# UC3842.net
KiCad netlist of a schematic drawn in Altium Designer
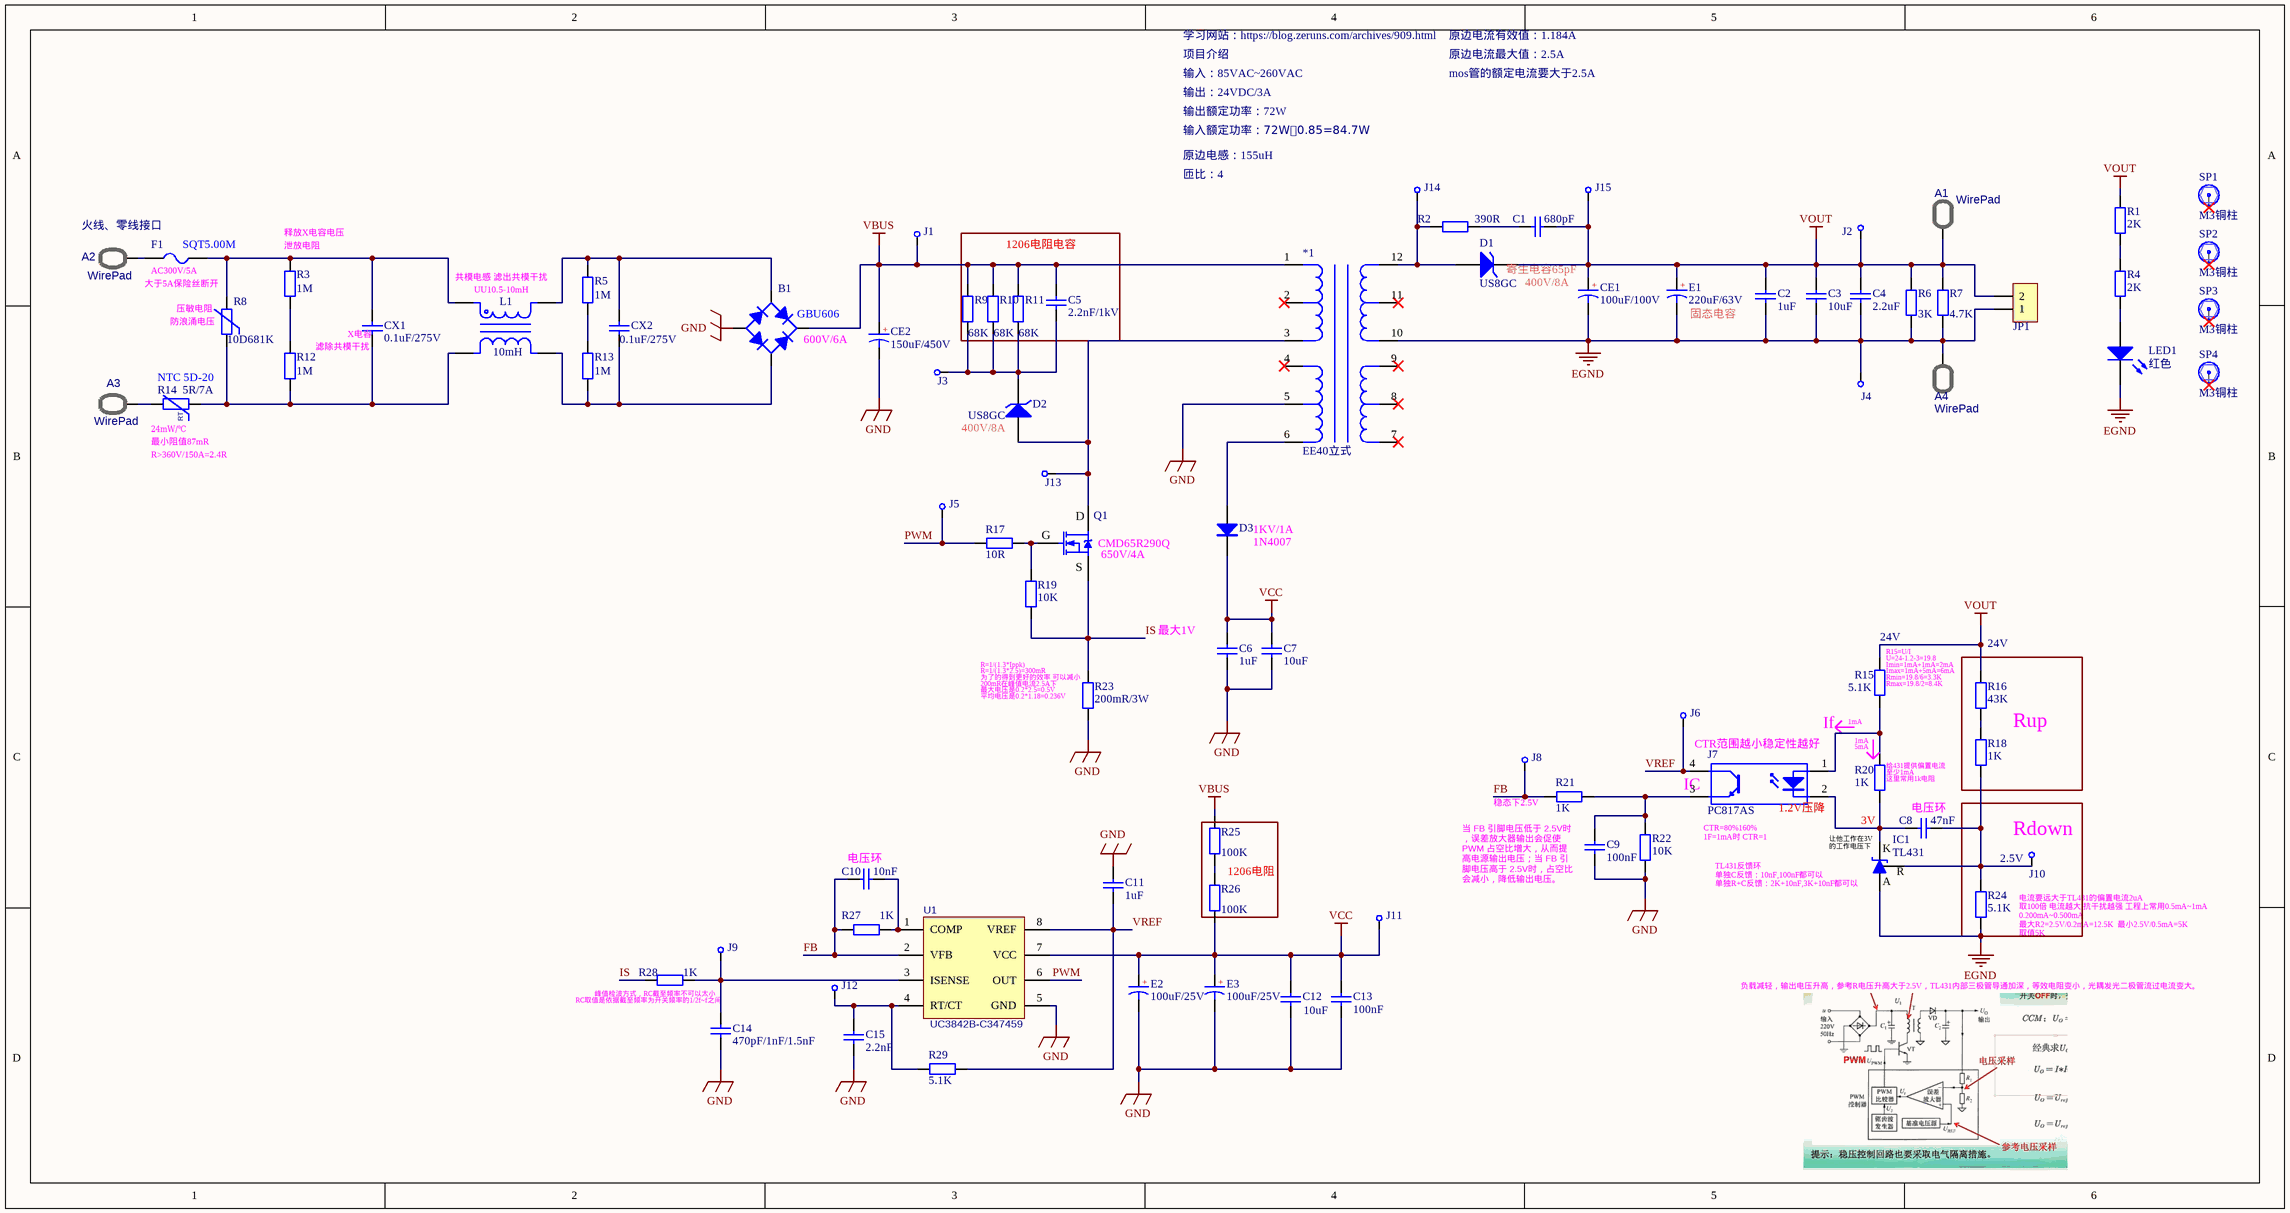
[diagram p0: UC3842第三版.SchDoc]

(export (version "E")
  (design (tool "Eeschema 10.0.6"))
  (components
    (comp (ref "*1") (value "EE40立式") (footprint "EE40立式") (libsource (lib "1.4 - 继电器-变压器") (part "EE40立式")))
    (comp (ref "A1")
      (value "WirePad")
      (footprint "WirePad-4.5x7")
      (description "线缆焊盘")
      (libsource (lib "无刷驱动-STC-无感-Lite3S") (part "WirePad"))
    )
    (comp (ref "A2")
      (value "WirePad")
      (footprint "WirePad-4.5x7")
      (description "线缆焊盘")
      (libsource (lib "无刷驱动-STC-无感-Lite3S") (part "WirePad"))
    )
    (comp (ref "A3")
      (value "WirePad")
      (footprint "WirePad-4.5x7")
      (description "线缆焊盘")
      (libsource (lib "无刷驱动-STC-无感-Lite3S") (part "WirePad"))
    )
    (comp (ref "A4")
      (value "WirePad")
      (footprint "WirePad-4.5x7")
      (description "线缆焊盘")
      (libsource (lib "无刷驱动-STC-无感-Lite3S") (part "WirePad"))
    )
    (comp (ref "B1")
      (value "GBU606")
      (footprint "GBU")
      (description "1KV/10A整流桥")
      (libsource (lib "0.2 - 二极管-TVS-ESD-整流桥-放电管") (part "GBU"))
    )
    (comp (ref "C1")
      (value "680pF")
      (footprint "C0805_L")
      (description "贴片电容/MLCC电容")
      (libsource (lib "0.1 - 电阻-电容-电感-保险丝-晶振-晶体-磁珠-电位器-法拉电容-馈通电容") (part "C"))
    )
    (comp (ref "C2")
      (value "1uF")
      (footprint "C0805_L")
      (description "贴片电容/MLCC电容")
      (libsource (lib "0.1 - 电阻-电容-电感-保险丝-晶振-晶体-磁珠-电位器-法拉电容-馈通电容") (part "C"))
    )
    (comp (ref "C3")
      (value "10uF")
      (footprint "C0805_L")
      (description "贴片电容/MLCC电容")
      (libsource (lib "0.1 - 电阻-电容-电感-保险丝-晶振-晶体-磁珠-电位器-法拉电容-馈通电容") (part "C"))
    )
    (comp (ref "C4")
      (value "2.2uF")
      (footprint "C0805_L")
      (description "贴片电容/MLCC电容")
      (libsource (lib "0.1 - 电阻-电容-电感-保险丝-晶振-晶体-磁珠-电位器-法拉电容-馈通电容") (part "C"))
    )
    (comp (ref "C5")
      (value "2.2nF/1kV")
      (footprint "C0805_L")
      (description "贴片电容/MLCC电容")
      (libsource (lib "0.1 - 电阻-电容-电感-保险丝-晶振-晶体-磁珠-电位器-法拉电容-馈通电容") (part "C"))
    )
    (comp (ref "C6")
      (value "1uF")
      (footprint "C0805_L")
      (description "贴片电容/MLCC电容")
      (libsource (lib "0.1 - 电阻-电容-电感-保险丝-晶振-晶体-磁珠-电位器-法拉电容-馈通电容") (part "C"))
    )
    (comp (ref "C7")
      (value "10uF")
      (footprint "C0805_L")
      (description "贴片电容/MLCC电容")
      (libsource (lib "0.1 - 电阻-电容-电感-保险丝-晶振-晶体-磁珠-电位器-法拉电容-馈通电容") (part "C"))
    )
    (comp (ref "C8")
      (value "47nF")
      (footprint "C0805_L")
      (description "贴片电容/MLCC电容")
      (libsource (lib "0.1 - 电阻-电容-电感-保险丝-晶振-晶体-磁珠-电位器-法拉电容-馈通电容") (part "C"))
    )
    (comp (ref "C9")
      (value "100nF")
      (footprint "C0805_L")
      (description "贴片电容/MLCC电容")
      (libsource (lib "0.1 - 电阻-电容-电感-保险丝-晶振-晶体-磁珠-电位器-法拉电容-馈通电容") (part "C"))
    )
    (comp (ref "C10")
      (value "10nF")
      (footprint "C0805_L")
      (description "贴片电容/MLCC电容")
      (libsource (lib "0.1 - 电阻-电容-电感-保险丝-晶振-晶体-磁珠-电位器-法拉电容-馈通电容") (part "C"))
    )
    (comp (ref "C11")
      (value "1uF")
      (footprint "C0805_L")
      (description "贴片电容/MLCC电容")
      (libsource (lib "0.1 - 电阻-电容-电感-保险丝-晶振-晶体-磁珠-电位器-法拉电容-馈通电容") (part "C"))
    )
    (comp (ref "C12")
      (value "10uF")
      (footprint "C0805_L")
      (description "贴片电容/MLCC电容")
      (libsource (lib "0.1 - 电阻-电容-电感-保险丝-晶振-晶体-磁珠-电位器-法拉电容-馈通电容") (part "C"))
    )
    (comp (ref "C13")
      (value "100nF")
      (footprint "C0805_L")
      (description "贴片电容/MLCC电容")
      (libsource (lib "0.1 - 电阻-电容-电感-保险丝-晶振-晶体-磁珠-电位器-法拉电容-馈通电容") (part "C"))
    )
    (comp (ref "C14")
      (value "470pF/1nF/1.5nF")
      (footprint "C0805_L")
      (description "贴片电容/MLCC电容")
      (libsource (lib "0.1 - 电阻-电容-电感-保险丝-晶振-晶体-磁珠-电位器-法拉电容-馈通电容") (part "C"))
    )
    (comp (ref "C15")
      (value "2.2nF")
      (footprint "C0805_L")
      (description "贴片电容/MLCC电容")
      (libsource (lib "0.1 - 电阻-电容-电感-保险丝-晶振-晶体-磁珠-电位器-法拉电容-馈通电容") (part "C"))
    )
    (comp (ref "CE1")
      (value "100uF/100V")
      (footprint "CE-5.0*10*16")
      (description "直插电解电容")
      (libsource (lib "0.1 - 电阻-电容-电感-保险丝-晶振-晶体-磁珠-电位器-法拉电容-馈通电容") (part "CE"))
    )
    (comp (ref "CE2")
      (value "150uF/450V")
      (footprint "CE-7.5*18*35.5-H - BK")
      (description "直插电解电容")
      (libsource (lib "0.1 - 电阻-电容-电感-保险丝-晶振-晶体-磁珠-电位器-法拉电容-馈通电容") (part "CE"))
    )
    (comp (ref "CX1")
      (value "0.1uF/275V")
      (footprint "CX 10*13*11")
      (description "安规X电容")
      (libsource (lib "0.1 - 电阻-电容-电感-保险丝-晶振-晶体-磁珠-电位器-法拉电容-馈通电容") (part "CX"))
    )
    (comp (ref "CX2")
      (value "0.1uF/275V")
      (footprint "CX 10*13*11")
      (description "安规X电容")
      (libsource (lib "0.1 - 电阻-电容-电感-保险丝-晶振-晶体-磁珠-电位器-法拉电容-馈通电容") (part "CX"))
    )
    (comp (ref "D1")
      (value "US8GC")
      (footprint "SMC")
      (description "5000W 24V TVS二极管")
      (libsource (lib "0.2 - 二极管-TVS-ESD-整流桥-放电管") (part "5.0SMDJ24A"))
    )
    (comp (ref "D2")
      (value "US8GC")
      (footprint "SMC")
      (description "5000W 24V TVS二极管")
      (libsource (lib "0.2 - 二极管-TVS-ESD-整流桥-放电管") (part "5.0SMDJ24A"))
    )
    (comp (ref "D3")
      (value "1N4007")
      (footprint "SMA")
      (description "整流二极管")
      (libsource (lib "0.2 - 二极管-TVS-ESD-整流桥-放电管") (part "1N4007"))
    )
    (comp (ref "E1")
      (value "220uF/63V")
      (footprint "CT 5.0*10*13 - R")
      (description "直插固态电容")
      (libsource (lib "0.1 - 电阻-电容-电感-保险丝-晶振-晶体-磁珠-电位器-法拉电容-馈通电容") (part "CS"))
    )
    (comp (ref "E2")
      (value "100uF/25V")
      (footprint "CE D(6.3*5.4)")
      (description "贴片电解电容")
      (libsource (lib "0.1 - 电阻-电容-电感-保险丝-晶振-晶体-磁珠-电位器-法拉电容-馈通电容") (part "CE_SMD"))
    )
    (comp (ref "E3")
      (value "100uF/25V")
      (footprint "CE D(6.3*5.4)")
      (description "贴片电解电容")
      (libsource (lib "0.1 - 电阻-电容-电感-保险丝-晶振-晶体-磁珠-电位器-法拉电容-馈通电容") (part "CE_SMD"))
    )
    (comp (ref "F1")
      (value "SQT5.00M")
      (footprint "FUSE-8.5x4.0-392Series")
      (description "方形保险丝")
      (libsource (lib "0.1 - 电阻-电容-电感-保险丝-晶振-晶体-磁珠-电位器-法拉电容-馈通电容") (part "FUSE-8.5*4.0*8.0"))
    )
    (comp (ref "IC1")
      (value "TL431")
      (footprint "SOT23-3N")
      (description "贴片可调基准稳压芯片")
      (libsource (lib "0.7 - 电源类芯片") (part "TL431_SMD"))
    )
    (comp (ref "J1")
      (value "CHECK")
      (footprint "CHECK-A")
      (description "测试点")
      (libsource (lib "课程库") (part "CHECK"))
    )
    (comp (ref "J2")
      (value "CHECK")
      (footprint "CHECK-A")
      (description "测试点")
      (libsource (lib "课程库") (part "CHECK"))
    )
    (comp (ref "J3")
      (value "CHECK")
      (footprint "CHECK-A")
      (description "测试点")
      (libsource (lib "课程库") (part "CHECK"))
    )
    (comp (ref "J4")
      (value "CHECK")
      (footprint "CHECK-A")
      (description "测试点")
      (libsource (lib "课程库") (part "CHECK"))
    )
    (comp (ref "J5")
      (value "CHECK")
      (footprint "CHECK-A")
      (description "测试点")
      (libsource (lib "课程库") (part "CHECK"))
    )
    (comp (ref "J6")
      (value "CHECK")
      (footprint "CHECK-A")
      (description "测试点")
      (libsource (lib "课程库") (part "CHECK"))
    )
    (comp (ref "J7")
      (value "PC817AS")
      (footprint "SOP4-W2.54_M")
      (description "1路开关光耦")
      (libsource (lib "0.3 - LED发光二极管-IR二极管_接收管-光耦") (part "TLP521-1"))
    )
    (comp (ref "J8")
      (value "CHECK")
      (footprint "CHECK-A")
      (description "测试点")
      (libsource (lib "课程库") (part "CHECK"))
    )
    (comp (ref "J9")
      (value "CHECK")
      (footprint "CHECK-A")
      (description "测试点")
      (libsource (lib "课程库") (part "CHECK"))
    )
    (comp (ref "J10")
      (value "CHECK")
      (footprint "CHECK-A")
      (description "测试点")
      (libsource (lib "课程库") (part "CHECK"))
    )
    (comp (ref "J11")
      (value "CHECK")
      (footprint "CHECK-A")
      (description "测试点")
      (libsource (lib "课程库") (part "CHECK"))
    )
    (comp (ref "J12")
      (value "CHECK")
      (footprint "CHECK-A")
      (description "测试点")
      (libsource (lib "课程库") (part "CHECK"))
    )
    (comp (ref "J13")
      (value "CHECK")
      (footprint "CHECK-A")
      (description "测试点")
      (libsource (lib "课程库") (part "CHECK"))
    )
    (comp (ref "J14")
      (value "CHECK")
      (footprint "CHECK-A")
      (description "测试点")
      (libsource (lib "课程库") (part "CHECK"))
    )
    (comp (ref "J15")
      (value "CHECK")
      (footprint "CHECK-A")
      (description "测试点")
      (libsource (lib "课程库") (part "CHECK"))
    )
    (comp (ref "JP1")
      (value "HDR-1X2")
      (footprint "KF301-5.0-2P")
      (description "2P接插件")
      (libsource (lib "6.0 - 5.0mm连接器(KF301-KF2EDGVHM)") (part "Header 2"))
    )
    (comp (ref "L1")
      (value "10mH")
      (footprint "UU9.8")
      (description "UU型共模电感")
      (libsource (lib "0.1 - 电阻-电容-电感-保险丝-晶振-晶体-磁珠-电位器-法拉电容-馈通电容") (part "L-UU"))
    )
    (comp (ref "LED1")
      (value "红色")
      (footprint "LED0805_G")
      (description "贴片LED")
      (libsource (lib "0.3 - LED发光二极管-IR二极管_接收管-光耦") (part "LED"))
    )
    (comp (ref "Q1")
      (value "CMD65R290Q")
      (footprint "TO252")
      (description "N沟道 100V/40A")
      (libsource (lib "0.4 - 三极管-场效应管-可控硅") (part "P40NF10L"))
    )
    (comp (ref "R1")
      (value "2K")
      (footprint "R0805_L")
      (description "贴片电阻")
      (libsource (lib "0.1 - 电阻-电容-电感-保险丝-晶振-晶体-磁珠-电位器-法拉电容-馈通电容") (part "R"))
    )
    (comp (ref "R2")
      (value "390R")
      (footprint "R0805_L")
      (description "贴片电阻")
      (libsource (lib "0.1 - 电阻-电容-电感-保险丝-晶振-晶体-磁珠-电位器-法拉电容-馈通电容") (part "R"))
    )
    (comp (ref "R3")
      (value "1M")
      (footprint "R1206_L")
      (description "贴片电阻")
      (libsource (lib "0.1 - 电阻-电容-电感-保险丝-晶振-晶体-磁珠-电位器-法拉电容-馈通电容") (part "R"))
    )
    (comp (ref "R4")
      (value "2K")
      (footprint "R0805_L")
      (description "贴片电阻")
      (libsource (lib "0.1 - 电阻-电容-电感-保险丝-晶振-晶体-磁珠-电位器-法拉电容-馈通电容") (part "R"))
    )
    (comp (ref "R5")
      (value "1M")
      (footprint "R1206_L")
      (description "贴片电阻")
      (libsource (lib "0.1 - 电阻-电容-电感-保险丝-晶振-晶体-磁珠-电位器-法拉电容-馈通电容") (part "R"))
    )
    (comp (ref "R6")
      (value "3K")
      (footprint "R1206_L")
      (description "贴片电阻")
      (libsource (lib "0.1 - 电阻-电容-电感-保险丝-晶振-晶体-磁珠-电位器-法拉电容-馈通电容") (part "R"))
    )
    (comp (ref "R7")
      (value "4.7K")
      (footprint "R1206_L")
      (description "贴片电阻")
      (libsource (lib "0.1 - 电阻-电容-电感-保险丝-晶振-晶体-磁珠-电位器-法拉电容-馈通电容") (part "R"))
    )
    (comp (ref "R8")
      (value "10D681K")
      (footprint "VDR 9D-4.5")
      (description "压敏电阻")
      (libsource (lib "0.1 - 电阻-电容-电感-保险丝-晶振-晶体-磁珠-电位器-法拉电容-馈通电容") (part "R_VSR"))
    )
    (comp (ref "R9")
      (value "68K")
      (footprint "R1206_L")
      (description "贴片电阻")
      (libsource (lib "0.1 - 电阻-电容-电感-保险丝-晶振-晶体-磁珠-电位器-法拉电容-馈通电容") (part "R"))
    )
    (comp (ref "R10")
      (value "68K")
      (footprint "R1206_L")
      (description "贴片电阻")
      (libsource (lib "0.1 - 电阻-电容-电感-保险丝-晶振-晶体-磁珠-电位器-法拉电容-馈通电容") (part "R"))
    )
    (comp (ref "R11")
      (value "68K")
      (footprint "R1206_L")
      (description "贴片电阻")
      (libsource (lib "0.1 - 电阻-电容-电感-保险丝-晶振-晶体-磁珠-电位器-法拉电容-馈通电容") (part "R"))
    )
    (comp (ref "R12")
      (value "1M")
      (footprint "R1206_L")
      (description "贴片电阻")
      (libsource (lib "0.1 - 电阻-电容-电感-保险丝-晶振-晶体-磁珠-电位器-法拉电容-馈通电容") (part "R"))
    )
    (comp (ref "R13")
      (value "1M")
      (footprint "R1206_L")
      (description "贴片电阻")
      (libsource (lib "0.1 - 电阻-电容-电感-保险丝-晶振-晶体-磁珠-电位器-法拉电容-馈通电容") (part "R"))
    )
    (comp (ref "R14")
      (value "5R/7A")
      (footprint "NTC-5D-20")
      (description "热敏电阻")
      (libsource (lib "0.1 - 电阻-电容-电感-保险丝-晶振-晶体-磁珠-电位器-法拉电容-馈通电容") (part "RT"))
    )
    (comp (ref "R15")
      (value "5.1K")
      (footprint "R0805_L")
      (description "贴片电阻")
      (libsource (lib "0.1 - 电阻-电容-电感-保险丝-晶振-晶体-磁珠-电位器-法拉电容-馈通电容") (part "R"))
    )
    (comp (ref "R16")
      (value "43K")
      (footprint "R0805_L")
      (description "贴片电阻")
      (libsource (lib "0.1 - 电阻-电容-电感-保险丝-晶振-晶体-磁珠-电位器-法拉电容-馈通电容") (part "R"))
    )
    (comp (ref "R17")
      (value "10R")
      (footprint "R0805_L")
      (description "贴片电阻")
      (libsource (lib "0.1 - 电阻-电容-电感-保险丝-晶振-晶体-磁珠-电位器-法拉电容-馈通电容") (part "R"))
    )
    (comp (ref "R18")
      (value "1K")
      (footprint "R0805_L")
      (description "贴片电阻")
      (libsource (lib "0.1 - 电阻-电容-电感-保险丝-晶振-晶体-磁珠-电位器-法拉电容-馈通电容") (part "R"))
    )
    (comp (ref "R19")
      (value "10K")
      (footprint "R0805_L")
      (description "贴片电阻")
      (libsource (lib "0.1 - 电阻-电容-电感-保险丝-晶振-晶体-磁珠-电位器-法拉电容-馈通电容") (part "R"))
    )
    (comp (ref "R20")
      (value "1K")
      (footprint "R0805_L")
      (description "贴片电阻")
      (libsource (lib "0.1 - 电阻-电容-电感-保险丝-晶振-晶体-磁珠-电位器-法拉电容-馈通电容") (part "R"))
    )
    (comp (ref "R21")
      (value "1K")
      (footprint "R0805_L")
      (description "贴片电阻")
      (libsource (lib "0.1 - 电阻-电容-电感-保险丝-晶振-晶体-磁珠-电位器-法拉电容-馈通电容") (part "R"))
    )
    (comp (ref "R22")
      (value "10K")
      (footprint "R0805_L")
      (description "贴片电阻")
      (libsource (lib "0.1 - 电阻-电容-电感-保险丝-晶振-晶体-磁珠-电位器-法拉电容-馈通电容") (part "R"))
    )
    (comp (ref "R23")
      (value "200mR/3W")
      (footprint "R2512_M")
      (description "贴片电阻")
      (libsource (lib "0.1 - 电阻-电容-电感-保险丝-晶振-晶体-磁珠-电位器-法拉电容-馈通电容") (part "R"))
    )
    (comp (ref "R24")
      (value "5.1K")
      (footprint "R0805_L")
      (description "贴片电阻")
      (libsource (lib "0.1 - 电阻-电容-电感-保险丝-晶振-晶体-磁珠-电位器-法拉电容-馈通电容") (part "R"))
    )
    (comp (ref "R25")
      (value "100K")
      (footprint "R1206_L")
      (description "贴片电阻")
      (libsource (lib "0.1 - 电阻-电容-电感-保险丝-晶振-晶体-磁珠-电位器-法拉电容-馈通电容") (part "R"))
    )
    (comp (ref "R26")
      (value "100K")
      (footprint "R1206_L")
      (description "贴片电阻")
      (libsource (lib "0.1 - 电阻-电容-电感-保险丝-晶振-晶体-磁珠-电位器-法拉电容-馈通电容") (part "R"))
    )
    (comp (ref "R27")
      (value "1K")
      (footprint "R0805_L")
      (description "贴片电阻")
      (libsource (lib "0.1 - 电阻-电容-电感-保险丝-晶振-晶体-磁珠-电位器-法拉电容-馈通电容") (part "R"))
    )
    (comp (ref "R28")
      (value "1K")
      (footprint "R0805_L")
      (description "贴片电阻")
      (libsource (lib "0.1 - 电阻-电容-电感-保险丝-晶振-晶体-磁珠-电位器-法拉电容-馈通电容") (part "R"))
    )
    (comp (ref "R29")
      (value "5.1K")
      (footprint "R0805_L")
      (description "贴片电阻")
      (libsource (lib "0.1 - 电阻-电容-电感-保险丝-晶振-晶体-磁珠-电位器-法拉电容-馈通电容") (part "R"))
    )
    (comp (ref "SP1")
      (value "M3铜柱")
      (footprint "M3x9_L")
      (description "铜柱")
      (libsource (lib "0.5 - 按键_开关_蜂鸣器_电池_测试点_Mark点_铜柱") (part "铜柱小焊盘"))
    )
    (comp (ref "SP2")
      (value "M3铜柱")
      (footprint "M3x9_L")
      (description "铜柱")
      (libsource (lib "0.5 - 按键_开关_蜂鸣器_电池_测试点_Mark点_铜柱") (part "铜柱小焊盘"))
    )
    (comp (ref "SP3")
      (value "M3铜柱")
      (footprint "M3x9_L")
      (description "铜柱")
      (libsource (lib "0.5 - 按键_开关_蜂鸣器_电池_测试点_Mark点_铜柱") (part "铜柱小焊盘"))
    )
    (comp (ref "SP4")
      (value "M3铜柱")
      (footprint "M3x9_L")
      (description "铜柱")
      (libsource (lib "0.5 - 按键_开关_蜂鸣器_电池_测试点_Mark点_铜柱") (part "铜柱小焊盘"))
    )
    (comp (ref "U1")
      (value "UC3842B-C347459")
      (footprint "SOIC-8_150mil")
      (description "开关电源芯片")
      (libsource (lib "0.7 - 电源类芯片") (part "UC3842"))
    )
  )
  (nets
    (net (code "1") (name "/FB") (class "Default")
      (node (ref "C10") (pin "2") (pinfunction "2_2") (pintype "passive"))
      (node (ref "J8") (pin "1") (pinfunction "1_1") (pintype "passive"))
      (node (ref "R21") (pin "2") (pinfunction "2_2") (pintype "passive"))
      (node (ref "R27") (pin "1") (pinfunction "1_1") (pintype "passive"))
      (node (ref "U1") (pin "2") (pinfunction "VFB_2") (pintype "passive"))
    )
    (net (code "2") (name "/IS") (class "Default")
      (node (ref "Q1") (pin "3") (pinfunction "S_3") (pintype "passive"))
      (node (ref "R19") (pin "2") (pinfunction "2_2") (pintype "passive"))
      (node (ref "R23") (pin "2") (pinfunction "2_2") (pintype "passive"))
      (node (ref "R28") (pin "1") (pinfunction "1_1") (pintype "passive"))
    )
    (net (code "3") (name "/PWM") (class "Default")
      (node (ref "J5") (pin "1") (pinfunction "1_1") (pintype "passive"))
      (node (ref "R17") (pin "2") (pinfunction "2_2") (pintype "passive"))
      (node (ref "U1") (pin "6") (pinfunction "OUT_6") (pintype "passive"))
    )
    (net (code "4") (name "/VREF") (class "Default")
      (node (ref "C11") (pin "2") (pinfunction "2_2") (pintype "passive"))
      (node (ref "J6") (pin "1") (pinfunction "1_1") (pintype "passive"))
      (node (ref "J7") (pin "4") (pinfunction "C_4") (pintype "passive"))
      (node (ref "R29") (pin "2") (pinfunction "2_2") (pintype "passive"))
      (node (ref "U1") (pin "8") (pinfunction "VREF_8") (pintype "passive"))
    )
    (net (code "5") (name "EGND") (class "Default")
      (node (ref "*1") (pin "10") (pinfunction "10_10") (pintype "passive"))
      (node (ref "A4") (pin "1") (pinfunction "1_1") (pintype "passive"))
      (node (ref "C2") (pin "1") (pinfunction "1_1") (pintype "passive"))
      (node (ref "C3") (pin "1") (pinfunction "1_1") (pintype "passive"))
      (node (ref "C4") (pin "1") (pinfunction "1_1") (pintype "passive"))
      (node (ref "CE1") (pin "2") (pinfunction "2_2") (pintype "passive"))
      (node (ref "E1") (pin "2") (pinfunction "2_2") (pintype "passive"))
      (node (ref "IC1") (pin "3") (pinfunction "A_3") (pintype "passive"))
      (node (ref "J4") (pin "1") (pinfunction "1_1") (pintype "passive"))
      (node (ref "JP1") (pin "1") (pinfunction "1_1") (pintype "passive"))
      (node (ref "LED1") (pin "2") (pinfunction "K_2") (pintype "passive"))
      (node (ref "R24") (pin "1") (pinfunction "1_1") (pintype "passive"))
      (node (ref "R6") (pin "1") (pinfunction "1_1") (pintype "passive"))
      (node (ref "R7") (pin "1") (pinfunction "1_1") (pintype "passive"))
    )
    (net (code "6") (name "GND") (class "Default")
      (node (ref "*1") (pin "5") (pinfunction "5_5") (pintype "passive"))
      (node (ref "B1") (pin "DC-") (pinfunction "DC-_DC-") (pintype "passive"))
      (node (ref "C11") (pin "1") (pinfunction "1_1") (pintype "passive"))
      (node (ref "C12") (pin "2") (pinfunction "2_2") (pintype "passive"))
      (node (ref "C13") (pin "2") (pinfunction "2_2") (pintype "passive"))
      (node (ref "C14") (pin "1") (pinfunction "1_1") (pintype "passive"))
      (node (ref "C15") (pin "1") (pinfunction "1_1") (pintype "passive"))
      (node (ref "C6") (pin "1") (pinfunction "1_1") (pintype "passive"))
      (node (ref "C7") (pin "1") (pinfunction "1_1") (pintype "passive"))
      (node (ref "C9") (pin "2") (pinfunction "2_2") (pintype "passive"))
      (node (ref "CE2") (pin "2") (pinfunction "2_2") (pintype "passive"))
      (node (ref "E2") (pin "2") (pinfunction "2_2") (pintype "passive"))
      (node (ref "E3") (pin "2") (pinfunction "2_2") (pintype "passive"))
      (node (ref "R22") (pin "2") (pinfunction "2_2") (pintype "passive"))
      (node (ref "R23") (pin "1") (pinfunction "1_1") (pintype "passive"))
      (node (ref "U1") (pin "5") (pinfunction "GND_5") (pintype "passive"))
    )
    (net (code "7") (name "Net-(A2-Pad1)") (class "Default")
      (node (ref "A2") (pin "1") (pinfunction "1_1") (pintype "passive"))
      (node (ref "F1") (pin "2") (pinfunction "2_2") (pintype "passive"))
    )
    (net (code "8") (name "Net-(A3-Pad1)") (class "Default")
      (node (ref "A3") (pin "1") (pinfunction "1_1") (pintype "passive"))
      (node (ref "R14") (pin "2") (pinfunction "2_2") (pintype "passive"))
    )
    (net (code "9") (name "Net-(B1-PadAC1)") (class "Default")
      (node (ref "B1") (pin "AC1") (pinfunction "AC1_AC1") (pintype "passive"))
      (node (ref "CX2") (pin "2") (pinfunction "2_2") (pintype "passive"))
      (node (ref "L1") (pin "2") (pinfunction "2_2") (pintype "passive"))
      (node (ref "R5") (pin "2") (pinfunction "2_2") (pintype "passive"))
    )
    (net (code "10") (name "Net-(B1-PadAC2)") (class "Default")
      (node (ref "B1") (pin "AC2") (pinfunction "AC2_AC2") (pintype "passive"))
      (node (ref "CX2") (pin "1") (pinfunction "1_1") (pintype "passive"))
      (node (ref "L1") (pin "3") (pinfunction "3_3") (pintype "passive"))
      (node (ref "R13") (pin "1") (pinfunction "1_1") (pintype "passive"))
    )
    (net (code "11") (name "Net-(C1-Pad2)") (class "Default")
      (node (ref "C1") (pin "2") (pinfunction "2_2") (pintype "passive"))
      (node (ref "R2") (pin "1") (pinfunction "1_1") (pintype "passive"))
    )
    (net (code "12") (name "Net-(CX1-Pad1)") (class "Default")
      (node (ref "CX1") (pin "1") (pinfunction "1_1") (pintype "passive"))
      (node (ref "L1") (pin "4") (pinfunction "4_4") (pintype "passive"))
      (node (ref "R12") (pin "1") (pinfunction "1_1") (pintype "passive"))
      (node (ref "R14") (pin "1") (pinfunction "1_1") (pintype "passive"))
      (node (ref "R8") (pin "1") (pinfunction "1_1") (pintype "passive"))
    )
    (net (code "13") (name "Net-(CX1-Pad2)") (class "Default")
      (node (ref "CX1") (pin "2") (pinfunction "2_2") (pintype "passive"))
      (node (ref "F1") (pin "1") (pinfunction "1_1") (pintype "passive"))
      (node (ref "L1") (pin "1") (pinfunction "1_1") (pintype "passive"))
      (node (ref "R3") (pin "2") (pinfunction "2_2") (pintype "passive"))
      (node (ref "R8") (pin "2") (pinfunction "2_2") (pintype "passive"))
    )
    (net (code "14") (name "Net-(D1-A)") (class "Default")
      (node (ref "*1") (pin "12") (pinfunction "12_12") (pintype "passive"))
      (node (ref "D1") (pin "1") (pinfunction "A_1") (pintype "passive"))
      (node (ref "J14") (pin "1") (pinfunction "1_1") (pintype "passive"))
      (node (ref "R2") (pin "2") (pinfunction "2_2") (pintype "passive"))
    )
    (net (code "15") (name "Net-(D2-A)") (class "Default")
      (node (ref "*1") (pin "3") (pinfunction "3_3") (pintype "passive"))
      (node (ref "D2") (pin "1") (pinfunction "A_1") (pintype "passive"))
      (node (ref "J13") (pin "1") (pinfunction "1_1") (pintype "passive"))
      (node (ref "Q1") (pin "2") (pintype "passive"))
    )
    (net (code "16") (name "Net-(D2-K)") (class "Default")
      (node (ref "C5") (pin "1") (pinfunction "1_1") (pintype "passive"))
      (node (ref "D2") (pin "2") (pinfunction "K_2") (pintype "passive"))
      (node (ref "J3") (pin "1") (pinfunction "1_1") (pintype "passive"))
      (node (ref "R10") (pin "1") (pinfunction "1_1") (pintype "passive"))
      (node (ref "R11") (pin "1") (pinfunction "1_1") (pintype "passive"))
      (node (ref "R9") (pin "1") (pinfunction "1_1") (pintype "passive"))
    )
    (net (code "17") (name "Net-(D3-A)") (class "Default")
      (node (ref "*1") (pin "6") (pinfunction "6_6") (pintype "passive"))
      (node (ref "D3") (pin "1") (pinfunction "A_1") (pintype "passive"))
    )
    (net (code "18") (name "Net-(IC1-K)") (class "Default")
      (node (ref "C8") (pin "2") (pinfunction "2_2") (pintype "passive"))
      (node (ref "IC1") (pin "2") (pinfunction "K_2") (pintype "passive"))
      (node (ref "J7") (pin "2") (pinfunction "K_2") (pintype "passive"))
      (node (ref "R20") (pin "1") (pinfunction "1_1") (pintype "passive"))
    )
    (net (code "19") (name "Net-(IC1-R)") (class "Default")
      (node (ref "C8") (pin "1") (pinfunction "1_1") (pintype "passive"))
      (node (ref "IC1") (pin "1") (pinfunction "R_1") (pintype "passive"))
      (node (ref "J10") (pin "1") (pinfunction "1_1") (pintype "passive"))
      (node (ref "R18") (pin "1") (pinfunction "1_1") (pintype "passive"))
      (node (ref "R24") (pin "2") (pinfunction "2_2") (pintype "passive"))
    )
    (net (code "20") (name "Net-(J7-A)") (class "Default")
      (node (ref "J7") (pin "1") (pinfunction "A_1") (pintype "passive"))
      (node (ref "R15") (pin "1") (pinfunction "1_1") (pintype "passive"))
      (node (ref "R20") (pin "2") (pinfunction "2_2") (pintype "passive"))
    )
    (net (code "21") (name "Net-(J7-E)") (class "Default")
      (node (ref "C9") (pin "1") (pinfunction "1_1") (pintype "passive"))
      (node (ref "J7") (pin "3") (pinfunction "E_3") (pintype "passive"))
      (node (ref "R21") (pin "1") (pinfunction "1_1") (pintype "passive"))
      (node (ref "R22") (pin "1") (pinfunction "1_1") (pintype "passive"))
    )
    (net (code "22") (name "Net-(LED1-A)") (class "Default")
      (node (ref "LED1") (pin "1") (pinfunction "A_1") (pintype "passive"))
      (node (ref "R4") (pin "1") (pinfunction "1_1") (pintype "passive"))
    )
    (net (code "23") (name "Net-(Q1-G)") (class "Default")
      (node (ref "Q1") (pin "1") (pinfunction "G_1") (pintype "passive"))
      (node (ref "R17") (pin "1") (pinfunction "1_1") (pintype "passive"))
      (node (ref "R19") (pin "1") (pinfunction "1_1") (pintype "passive"))
    )
    (net (code "24") (name "Net-(R1-Pad1)") (class "Default")
      (node (ref "R1") (pin "1") (pinfunction "1_1") (pintype "passive"))
      (node (ref "R4") (pin "2") (pinfunction "2_2") (pintype "passive"))
    )
    (net (code "25") (name "Net-(R12-Pad2)") (class "Default")
      (node (ref "R12") (pin "2") (pinfunction "2_2") (pintype "passive"))
      (node (ref "R3") (pin "1") (pinfunction "1_1") (pintype "passive"))
    )
    (net (code "26") (name "Net-(R13-Pad2)") (class "Default")
      (node (ref "R13") (pin "2") (pinfunction "2_2") (pintype "passive"))
      (node (ref "R5") (pin "1") (pinfunction "1_1") (pintype "passive"))
    )
    (net (code "27") (name "Net-(R16-Pad1)") (class "Default")
      (node (ref "R16") (pin "1") (pinfunction "1_1") (pintype "passive"))
      (node (ref "R18") (pin "2") (pinfunction "2_2") (pintype "passive"))
    )
    (net (code "28") (name "Net-(R25-Pad1)") (class "Default")
      (node (ref "R25") (pin "1") (pinfunction "1_1") (pintype "passive"))
      (node (ref "R26") (pin "2") (pinfunction "2_2") (pintype "passive"))
    )
    (net (code "29") (name "Net-(U1-COMP)") (class "Default")
      (node (ref "C10") (pin "1") (pinfunction "1_1") (pintype "passive"))
      (node (ref "R27") (pin "2") (pinfunction "2_2") (pintype "passive"))
      (node (ref "U1") (pin "1") (pinfunction "COMP_1") (pintype "passive"))
    )
    (net (code "30") (name "Net-(U1-ISENSE)") (class "Default")
      (node (ref "C14") (pin "2") (pinfunction "2_2") (pintype "passive"))
      (node (ref "J9") (pin "1") (pinfunction "1_1") (pintype "passive"))
      (node (ref "R28") (pin "2") (pinfunction "2_2") (pintype "passive"))
      (node (ref "U1") (pin "3") (pinfunction "ISENSE_3") (pintype "passive"))
    )
    (net (code "31") (name "Net-(U1-RT{slash}CT)") (class "Default")
      (node (ref "C15") (pin "2") (pinfunction "2_2") (pintype "passive"))
      (node (ref "J12") (pin "1") (pinfunction "1_1") (pintype "passive"))
      (node (ref "R29") (pin "1") (pinfunction "1_1") (pintype "passive"))
      (node (ref "U1") (pin "4") (pinfunction "RT/CT_4") (pintype "passive"))
    )
    (net (code "32") (name "VBUS") (class "Default")
      (node (ref "*1") (pin "1") (pinfunction "1_1") (pintype "passive"))
      (node (ref "B1") (pin "DC+") (pinfunction "DC+_DC+") (pintype "passive"))
      (node (ref "C5") (pin "2") (pinfunction "2_2") (pintype "passive"))
      (node (ref "CE2") (pin "1") (pinfunction "1_1") (pintype "passive"))
      (node (ref "J1") (pin "1") (pinfunction "1_1") (pintype "passive"))
      (node (ref "R10") (pin "2") (pinfunction "2_2") (pintype "passive"))
      (node (ref "R11") (pin "2") (pinfunction "2_2") (pintype "passive"))
      (node (ref "R25") (pin "2") (pinfunction "2_2") (pintype "passive"))
      (node (ref "R9") (pin "2") (pinfunction "2_2") (pintype "passive"))
    )
    (net (code "33") (name "VCC") (class "Default")
      (node (ref "C12") (pin "1") (pinfunction "1_1") (pintype "passive"))
      (node (ref "C13") (pin "1") (pinfunction "1_1") (pintype "passive"))
      (node (ref "C6") (pin "2") (pinfunction "2_2") (pintype "passive"))
      (node (ref "C7") (pin "2") (pinfunction "2_2") (pintype "passive"))
      (node (ref "D3") (pin "2") (pinfunction "K_2") (pintype "passive"))
      (node (ref "E2") (pin "1") (pinfunction "1_1") (pintype "passive"))
      (node (ref "E3") (pin "1") (pinfunction "1_1") (pintype "passive"))
      (node (ref "J11") (pin "1") (pinfunction "1_1") (pintype "passive"))
      (node (ref "R26") (pin "1") (pinfunction "1_1") (pintype "passive"))
      (node (ref "U1") (pin "7") (pinfunction "VCC_7") (pintype "passive"))
    )
    (net (code "34") (name "VOUT") (class "Default")
      (node (ref "A1") (pin "1") (pinfunction "1_1") (pintype "passive"))
      (node (ref "C1") (pin "1") (pinfunction "1_1") (pintype "passive"))
      (node (ref "C2") (pin "2") (pinfunction "2_2") (pintype "passive"))
      (node (ref "C3") (pin "2") (pinfunction "2_2") (pintype "passive"))
      (node (ref "C4") (pin "2") (pinfunction "2_2") (pintype "passive"))
      (node (ref "CE1") (pin "1") (pinfunction "1_1") (pintype "passive"))
      (node (ref "D1") (pin "2") (pinfunction "K_2") (pintype "passive"))
      (node (ref "E1") (pin "1") (pinfunction "1_1") (pintype "passive"))
      (node (ref "J15") (pin "1") (pinfunction "1_1") (pintype "passive"))
      (node (ref "J2") (pin "1") (pinfunction "1_1") (pintype "passive"))
      (node (ref "JP1") (pin "2") (pinfunction "2_2") (pintype "passive"))
      (node (ref "R1") (pin "2") (pinfunction "2_2") (pintype "passive"))
      (node (ref "R15") (pin "2") (pinfunction "2_2") (pintype "passive"))
      (node (ref "R16") (pin "2") (pinfunction "2_2") (pintype "passive"))
      (node (ref "R6") (pin "2") (pinfunction "2_2") (pintype "passive"))
      (node (ref "R7") (pin "2") (pinfunction "2_2") (pintype "passive"))
    )
    (net (code "35") (name "unconnected-(*1-Pad2)") (class "Default")
      (node (ref "*1") (pin "2") (pinfunction "2_2") (pintype "passive+no_connect"))
    )
    (net (code "36") (name "unconnected-(*1-Pad4)") (class "Default")
      (node (ref "*1") (pin "4") (pinfunction "4_4") (pintype "passive+no_connect"))
    )
    (net (code "37") (name "unconnected-(*1-Pad7)") (class "Default")
      (node (ref "*1") (pin "7") (pinfunction "7_7") (pintype "passive+no_connect"))
    )
    (net (code "38") (name "unconnected-(*1-Pad8)") (class "Default")
      (node (ref "*1") (pin "8") (pinfunction "8_8") (pintype "passive+no_connect"))
    )
    (net (code "39") (name "unconnected-(*1-Pad9)") (class "Default")
      (node (ref "*1") (pin "9") (pinfunction "9_9") (pintype "passive+no_connect"))
    )
    (net (code "40") (name "unconnected-(*1-Pad11)") (class "Default")
      (node (ref "*1") (pin "11") (pinfunction "11_11") (pintype "passive+no_connect"))
    )
    (net (code "41") (name "unconnected-(SP1-Pad1)") (class "Default")
      (node (ref "SP1") (pin "1") (pinfunction "1_1") (pintype "passive+no_connect"))
    )
    (net (code "42") (name "unconnected-(SP2-Pad1)") (class "Default")
      (node (ref "SP2") (pin "1") (pinfunction "1_1") (pintype "passive+no_connect"))
    )
    (net (code "43") (name "unconnected-(SP3-Pad1)") (class "Default")
      (node (ref "SP3") (pin "1") (pinfunction "1_1") (pintype "passive+no_connect"))
    )
    (net (code "44") (name "unconnected-(SP4-Pad1)") (class "Default")
      (node (ref "SP4") (pin "1") (pinfunction "1_1") (pintype "passive+no_connect"))
    )
  )
)
